# SCH_DISPLAY_T12.net
KiCad netlist of a schematic drawn in Altium Designer
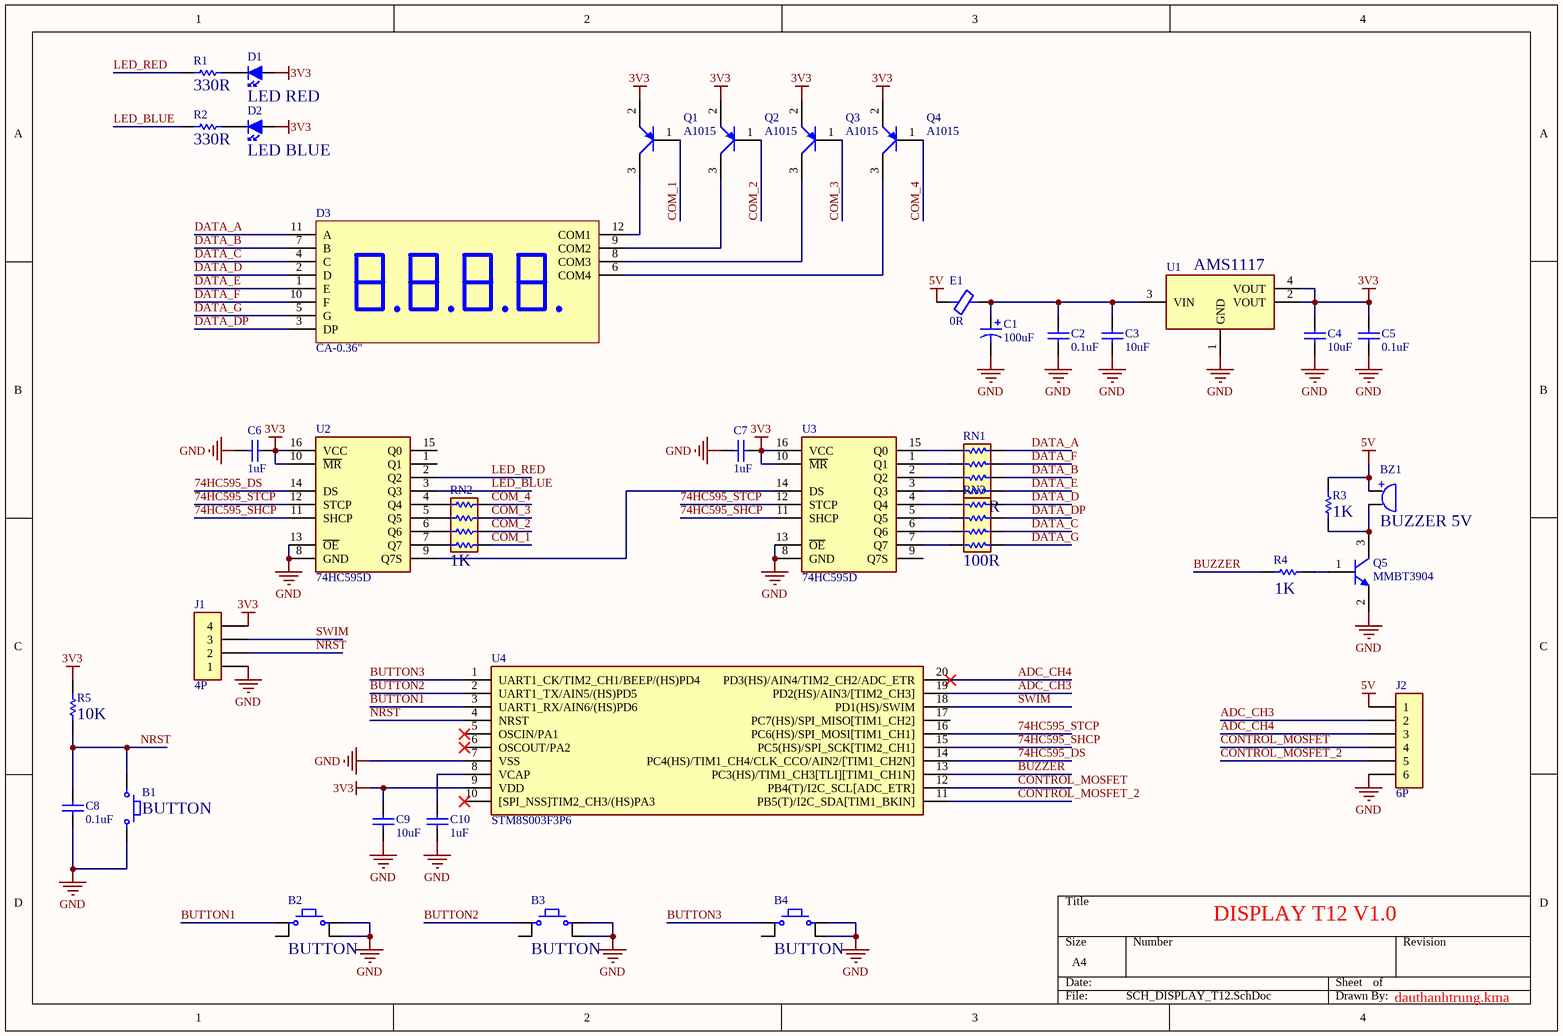
[diagram p0: SCH_DISPLAY_T12.SchDoc]

(export (version "E")
  (design (tool "Eeschema 10.0.6"))
  (components
    (comp (ref "B1")
      (value "BUTTON")
      (footprint "BUTTON-SMD-2P-3x6x2.5MM")
      (description "Nút nhấn 2 chân dán 3x6x2.5mm")
      (fields (field (name "PARTNUMBER") "CLA1750") (field (name "CREATOR") "dauthanhtrung.kma"))
      (libsource (lib "KMA-lib") (part "BUTTON-2PIN"))
    )
    (comp (ref "B2")
      (value "BUTTON")
      (footprint "BUTTON-SMD-4P-6X6X5MM")
      (description "Nút nhấn 4 chân 6x6x5mm SMD")
      (fields (field (name "PARTNUMBER") "CLA1760") (field (name "CREATOR") "dauthanhtrung.kma"))
      (libsource (lib "KMA-lib") (part "BUTTON-4PIN"))
    )
    (comp (ref "B3")
      (value "BUTTON")
      (footprint "BUTTON-SMD-4P-6X6X5MM")
      (description "Nút nhấn 4 chân 6x6x5mm SMD")
      (fields (field (name "PARTNUMBER") "CLA1760") (field (name "CREATOR") "dauthanhtrung.kma"))
      (libsource (lib "KMA-lib") (part "BUTTON-4PIN"))
    )
    (comp (ref "B4")
      (value "BUTTON")
      (footprint "BUTTON-SMD-4P-6X6X5MM")
      (description "Nút nhấn 4 chân 6x6x5mm SMD")
      (fields (field (name "PARTNUMBER") "CLA1760") (field (name "CREATOR") "dauthanhtrung.kma"))
      (libsource (lib "KMA-lib") (part "BUTTON-4PIN"))
    )
    (comp (ref "BZ1")
      (value "BUZZER 5V")
      (footprint "BUZZER_12095")
      (description "Còi chíp 5V 12095 12x9.5mm")
      (fields (field (name "PARTNUMBER") "CLA2022") (field (name "CREATOR") "dauthanhtrung.kma"))
      (libsource (lib "KMA-lib") (part "BUZZER"))
    )
    (comp (ref "C1")
      (value "100uF")
      (footprint "CAPP-ALU-SMD-6MM")
      (description "Tụ nhôm 16V 100uF 6.3x5.4mm")
      (fields (field (name "PARTNUMBER") "CLA1046") (field (name "CREATOR") "dauthanhtrung.kma"))
      (libsource (lib "KMA-lib") (part "CAPP"))
    )
    (comp (ref "C2")
      (value "0.1uF")
      (footprint "CAP_0603")
      (description "Tụ dán 0603 104-100nF 0.1uF 50V 10%")
      (fields (field (name "PARTNUMBER") "CLA4098") (field (name "CREATOR") "dauthanhtrung.kma"))
      (libsource (lib "KMA-lib") (part "CAP"))
    )
    (comp (ref "C3")
      (value "10uF")
      (footprint "CAP_0805")
      (description "Tụ dán 0805 106-10uF 16V 10%")
      (fields (field (name "PARTNUMBER") "CLA4020") (field (name "CREATOR") "dauthanhtrung.kma"))
      (libsource (lib "KMA-lib") (part "CAP"))
    )
    (comp (ref "C4")
      (value "10uF")
      (footprint "CAP_0805")
      (description "Tụ dán 0805 106-10uF 16V 10%")
      (fields (field (name "PARTNUMBER") "CLA4020") (field (name "CREATOR") "dauthanhtrung.kma"))
      (libsource (lib "KMA-lib") (part "CAP"))
    )
    (comp (ref "C5")
      (value "0.1uF")
      (footprint "CAP_0603")
      (description "Tụ dán 0603 104-100nF 0.1uF 50V 10%")
      (fields (field (name "PARTNUMBER") "CLA4098") (field (name "CREATOR") "dauthanhtrung.kma"))
      (libsource (lib "KMA-lib") (part "CAP"))
    )
    (comp (ref "C6")
      (value "1uF")
      (footprint "CAP_0603")
      (description "Tụ dán 0603 105-1uF 25V 10%")
      (fields (field (name "PARTNUMBER") "CLA4103") (field (name "CREATOR") "dauthanhtrung.kma"))
      (libsource (lib "KMA-lib") (part "CAP"))
    )
    (comp (ref "C7")
      (value "1uF")
      (footprint "CAP_0603")
      (description "Tụ dán 0603 105-1uF 25V 10%")
      (fields (field (name "PARTNUMBER") "CLA4103") (field (name "CREATOR") "dauthanhtrung.kma"))
      (libsource (lib "KMA-lib") (part "CAP"))
    )
    (comp (ref "C8")
      (value "0.1uF")
      (footprint "CAP_0603")
      (description "Tụ dán 0603 104-100nF 0.1uF 50V 10%")
      (fields (field (name "PARTNUMBER") "CLA4098") (field (name "CREATOR") "dauthanhtrung.kma"))
      (libsource (lib "KMA-lib") (part "CAP"))
    )
    (comp (ref "C9")
      (value "10uF")
      (footprint "CAP_0805")
      (description "Tụ dán 0805 106-10uF 16V 10%")
      (fields (field (name "PARTNUMBER") "CLA4020") (field (name "CREATOR") "dauthanhtrung.kma"))
      (libsource (lib "KMA-lib") (part "CAP"))
    )
    (comp (ref "C10")
      (value "1uF")
      (footprint "CAP_0603")
      (description "Tụ dán 0603 105-1uF 25V 10%")
      (fields (field (name "PARTNUMBER") "CLA4103") (field (name "CREATOR") "dauthanhtrung.kma"))
      (libsource (lib "KMA-lib") (part "CAP"))
    )
    (comp (ref "D1")
      (value "LED RED")
      (footprint "LED-0603-RED")
      (description "LED dán 0603 màu đỏ")
      (fields (field (name "PARTNUMBER") "CLA3853") (field (name "CREATOR") "dauthanhtrung.kma"))
      (libsource (lib "KMA-lib") (part "LED"))
    )
    (comp (ref "D2")
      (value "LED BLUE")
      (footprint "LED-0603-BLUE")
      (description "LED dán 0603 màu xanh dương")
      (fields (field (name "PARTNUMBER") "CLA3855") (field (name "CREATOR") "dauthanhtrung.kma"))
      (libsource (lib "KMA-lib") (part "LED"))
    )
    (comp (ref "D3")
      (value "CA-0.36\"")
      (footprint "LED7SEG-0.36-4")
      (description "LED 7 thanh 0.36 inch 4 số màu đỏ A chung 3642BS")
      (fields (field (name "PARTNUMBER") "CLA2087") (field (name "CREATOR") "dauthanhtrung.kma"))
      (libsource (lib "KMA-lib") (part "LED7SEG-0.36-4"))
    )
    (comp (ref "E1")
      (value "0R")
      (footprint "FB_0805")
      (description "Ferrite Beads 0805 0R")
      (fields (field (name "PARTNUMBER") "CL07788") (field (name "CREATOR") "dauthanhtrung.kma"))
      (libsource (lib "KMA-lib") (part "FB"))
    )
    (comp (ref "J1")
      (value "4P")
      (footprint "JUMP-2.54-MALE-4P")
      (description "Jump đực đơn 2.54mm 4P chân thẳng")
      (fields (field (name "PARTNUMBER") "JUMP-2.54-MALE-4P") (field (name "CREATOR") "dauthanhtrung.kma"))
      (libsource (lib "KMA-lib") (part "CON-4PIN"))
    )
    (comp (ref "J2")
      (value "6P")
      (footprint "XH2.54-6P")
      (description "Header đực 6P XH2.54-6P chân thẳng")
      (fields (field (name "PARTNUMBER") "CLA1882") (field (name "CREATOR") "dauthanhtrung.kma"))
      (libsource (lib "KMA-lib") (part "CON-6PIN"))
    )
    (comp (ref "Q1")
      (value "A1015")
      (footprint "SOT-23-132")
      (description "A1015 PNP Transistor 0.15A 60V SOT-23")
      (fields (field (name "PARTNUMBER") "CL08753") (field (name "CREATOR") "dauthanhtrung.kma"))
      (libsource (lib "KMA-lib") (part "PNP"))
    )
    (comp (ref "Q2")
      (value "A1015")
      (footprint "SOT-23-132")
      (description "A1015 PNP Transistor 0.15A 60V SOT-23")
      (fields (field (name "PARTNUMBER") "CL08753") (field (name "CREATOR") "dauthanhtrung.kma"))
      (libsource (lib "KMA-lib") (part "PNP"))
    )
    (comp (ref "Q3")
      (value "A1015")
      (footprint "SOT-23-132")
      (description "A1015 PNP Transistor 0.15A 60V SOT-23")
      (fields (field (name "PARTNUMBER") "CL08753") (field (name "CREATOR") "dauthanhtrung.kma"))
      (libsource (lib "KMA-lib") (part "PNP"))
    )
    (comp (ref "Q4")
      (value "A1015")
      (footprint "SOT-23-132")
      (description "A1015 PNP Transistor 0.15A 60V SOT-23")
      (fields (field (name "PARTNUMBER") "CL08753") (field (name "CREATOR") "dauthanhtrung.kma"))
      (libsource (lib "KMA-lib") (part "PNP"))
    )
    (comp (ref "Q5")
      (value "MMBT3904")
      (footprint "SOT-23-132")
      (description "2N3904 MMBT3904 1AM NPN Transistor 0.2A 40V SOT-23")
      (fields (field (name "PARTNUMBER") "CL00042") (field (name "CREATOR") "dauthanhtrung.kma"))
      (libsource (lib "KMA-lib") (part "NPN"))
    )
    (comp (ref "R1")
      (value "330R")
      (footprint "RES_0603")
      (description "Điện trở dán 0603 330R 1%")
      (fields (field (name "PARTNUMBER") "CL06621") (field (name "CREATOR") "dauthanhtrung.kma"))
      (libsource (lib "KMA-lib") (part "RES"))
    )
    (comp (ref "R2")
      (value "330R")
      (footprint "RES_0603")
      (description "Điện trở dán 0603 330R 1%")
      (fields (field (name "PARTNUMBER") "CL06621") (field (name "CREATOR") "dauthanhtrung.kma"))
      (libsource (lib "KMA-lib") (part "RES"))
    )
    (comp (ref "R3")
      (value "1K")
      (footprint "RES_0603")
      (description "Điện trở dán 0603 1K 1%")
      (fields (field (name "PARTNUMBER") "CLA0742") (field (name "CREATOR") "dauthanhtrung.kma"))
      (libsource (lib "KMA-lib") (part "RES"))
    )
    (comp (ref "R4")
      (value "1K")
      (footprint "RES_0603")
      (description "Điện trở dán 0603 1K 1%")
      (fields (field (name "PARTNUMBER") "CLA0742") (field (name "CREATOR") "dauthanhtrung.kma"))
      (libsource (lib "KMA-lib") (part "RES"))
    )
    (comp (ref "R5")
      (value "10K")
      (footprint "RES_0603")
      (description "Điện trở dán 0603 10K 1%")
      (fields (field (name "PARTNUMBER") "CLA0759") (field (name "CREATOR") "dauthanhtrung.kma"))
      (libsource (lib "KMA-lib") (part "RES"))
    )
    (comp (ref "RN1")
      (value "100R")
      (footprint "RES_ARRAY_0603X4")
      (description "Điện trở băng 0603x4 100R 8P4R")
      (fields (field (name "PARTNUMBER") "CLA0906") (field (name "CREATOR") "dauthanhtrung.kma"))
      (libsource (lib "") (part "RES-ARRAY_1"))
    )
    (comp (ref "RN2")
      (value "1K")
      (footprint "RES_ARRAY_0603X4")
      (description "Điện trở băng 0603x4 1K 8P4R")
      (fields (field (name "PARTNUMBER") "CLA0909") (field (name "CREATOR") "dauthanhtrung.kma"))
      (libsource (lib "KMA-lib") (part "RES-ARRAY"))
    )
    (comp (ref "RN3")
      (value "100R")
      (footprint "RES_ARRAY_0603X4")
      (description "Điện trở băng 0603x4 100R 8P4R")
      (fields (field (name "PARTNUMBER") "CLA0906") (field (name "CREATOR") "dauthanhtrung.kma"))
      (libsource (lib "") (part "RES-ARRAY_1"))
    )
    (comp (ref "U1")
      (value "AMS1117")
      (footprint "SOT-223")
      (description "AMS1117-3.3V IC ổn áp 3.3V 1A SOT-223")
      (fields (field (name "PARTNUMBER") "CL00249") (field (name "CREATOR") "dauthanhtrung.kma"))
      (libsource (lib "KMA-lib") (part "AMS1117"))
    )
    (comp (ref "U2")
      (value "74HC595D")
      (footprint "SOIC-16")
      (description "74HC595D SOP-16 3.9mm chính hãng NXP")
      (fields
        (field (name "MP") "STM8S003F3P6")
        (field (name "MF") "STMicroelectronics")
        (field (name "CREATOR") "dauthanhtrung.kma")
      )
      (libsource (lib "KMA-lib") (part "74HC595"))
    )
    (comp (ref "U3")
      (value "74HC595D")
      (footprint "SOIC-16")
      (description "74HC595D SOP-16 3.9mm chính hãng NXP")
      (fields
        (field (name "MP") "STM8S003F3P6")
        (field (name "MF") "STMicroelectronics")
        (field (name "CREATOR") "dauthanhtrung.kma")
      )
      (libsource (lib "KMA-lib") (part "74HC595"))
    )
    (comp (ref "U4")
      (value "STM8S003F3P6")
      (footprint "TSSOP-20")
      (description "STM8S003F3P6 TSSOP-20")
      (fields
        (field (name "MF") "STMicroelectronics")
        (field (name "PARTNUMBER") "CL00897")
        (field (name "CREATOR") "dauthanhtrung.kma")
      )
      (libsource (lib "KMA-lib") (part "STM8S003F3P6"))
    )
  )
  (nets
    (net (code "1") (name "/74HC595_DS") (class "Default")
      (node (ref "U2") (pin "14") (pinfunction "DS_14") (pintype "passive"))
      (node (ref "U4") (pin "14") (pinfunction "PC4(HS)/TIM1_CH4/CLK_CCO/AIN2/[TIM1_CH2N]_14") (pintype "passive"))
    )
    (net (code "2") (name "/74HC595_SHCP") (class "Default")
      (node (ref "U2") (pin "11") (pinfunction "SHCP_11") (pintype "passive"))
      (node (ref "U3") (pin "11") (pinfunction "SHCP_11") (pintype "passive"))
      (node (ref "U4") (pin "15") (pinfunction "PC5(HS)/SPI_SCK[TIM2_CH1]_15") (pintype "passive"))
    )
    (net (code "3") (name "/74HC595_STCP") (class "Default")
      (node (ref "U2") (pin "12") (pinfunction "STCP_12") (pintype "passive"))
      (node (ref "U3") (pin "12") (pinfunction "STCP_12") (pintype "passive"))
      (node (ref "U4") (pin "16") (pinfunction "PC6(HS)/SPI_MOSI[TIM1_CH1]_16") (pintype "passive"))
    )
    (net (code "4") (name "/ADC_CH3") (class "Default")
      (node (ref "J2") (pin "2") (pinfunction "2_2") (pintype "passive"))
      (node (ref "U4") (pin "19") (pinfunction "PD2(HS)/AIN3/[TIM2_CH3]_19") (pintype "passive"))
    )
    (net (code "5") (name "/ADC_CH4") (class "Default")
      (node (ref "J2") (pin "3") (pinfunction "3_3") (pintype "passive"))
      (node (ref "U4") (pin "20") (pinfunction "PD3(HS)/AIN4/TIM2_CH2/ADC_ETR_20") (pintype "passive"))
    )
    (net (code "6") (name "/BUTTON1") (class "Default")
      (node (ref "B2") (pin "1") (pinfunction "1_1") (pintype "passive"))
      (node (ref "U4") (pin "3") (pinfunction "UART1_RX/AIN6/(HS)PD6_3") (pintype "passive"))
    )
    (net (code "7") (name "/BUTTON2") (class "Default")
      (node (ref "B3") (pin "1") (pinfunction "1_1") (pintype "passive"))
      (node (ref "U4") (pin "2") (pinfunction "UART1_TX/AIN5/(HS)PD5_2") (pintype "passive"))
    )
    (net (code "8") (name "/BUTTON3") (class "Default")
      (node (ref "B4") (pin "1") (pinfunction "1_1") (pintype "passive"))
      (node (ref "U4") (pin "1") (pinfunction "UART1_CK/TIM2_CH1/BEEP/(HS)PD4_1") (pintype "passive"))
    )
    (net (code "9") (name "/BUZZER") (class "Default")
      (node (ref "R4") (pin "1") (pinfunction "1_1") (pintype "passive"))
      (node (ref "U4") (pin "13") (pinfunction "PC3(HS)/TIM1_CH3[TLI][TIM1_CH1N]_13") (pintype "passive"))
    )
    (net (code "10") (name "/COM_1") (class "Default")
      (node (ref "Q1") (pin "1") (pinfunction "B_1") (pintype "passive"))
      (node (ref "RN2") (pin "1") (pinfunction "1_1") (pintype "passive"))
    )
    (net (code "11") (name "/COM_2") (class "Default")
      (node (ref "Q2") (pin "1") (pinfunction "B_1") (pintype "passive"))
      (node (ref "RN2") (pin "2") (pinfunction "2_2") (pintype "passive"))
    )
    (net (code "12") (name "/COM_3") (class "Default")
      (node (ref "Q3") (pin "1") (pinfunction "B_1") (pintype "passive"))
      (node (ref "RN2") (pin "3") (pinfunction "3_3") (pintype "passive"))
    )
    (net (code "13") (name "/COM_4") (class "Default")
      (node (ref "Q4") (pin "1") (pinfunction "B_1") (pintype "passive"))
      (node (ref "RN2") (pin "4") (pinfunction "4_4") (pintype "passive"))
    )
    (net (code "14") (name "/CONTROL_MOSFET") (class "Default")
      (node (ref "J2") (pin "4") (pinfunction "4_4") (pintype "passive"))
      (node (ref "U4") (pin "12") (pinfunction "PB4(T)/I2C_SCL[ADC_ETR]_12") (pintype "passive"))
    )
    (net (code "15") (name "/CONTROL_MOSFET_2") (class "Default")
      (node (ref "J2") (pin "5") (pinfunction "5_5") (pintype "passive"))
      (node (ref "U4") (pin "11") (pinfunction "PB5(T)/I2C_SDA[TIM1_BKIN]_11") (pintype "passive"))
    )
    (net (code "16") (name "/DATA_A") (class "Default")
      (node (ref "D3") (pin "11") (pinfunction "A_11") (pintype "passive"))
      (node (ref "RN1") (pin "1") (pinfunction "1_1") (pintype "passive"))
    )
    (net (code "17") (name "/DATA_B") (class "Default")
      (node (ref "D3") (pin "7") (pinfunction "B_7") (pintype "passive"))
      (node (ref "RN1") (pin "3") (pinfunction "3_3") (pintype "passive"))
    )
    (net (code "18") (name "/DATA_C") (class "Default")
      (node (ref "D3") (pin "4") (pinfunction "C_4") (pintype "passive"))
      (node (ref "RN3") (pin "3") (pinfunction "3_3") (pintype "passive"))
    )
    (net (code "19") (name "/DATA_D") (class "Default")
      (node (ref "D3") (pin "2") (pinfunction "D_2") (pintype "passive"))
      (node (ref "RN3") (pin "1") (pinfunction "1_1") (pintype "passive"))
    )
    (net (code "20") (name "/DATA_DP") (class "Default")
      (node (ref "D3") (pin "3") (pinfunction "DP_3") (pintype "passive"))
      (node (ref "RN3") (pin "2") (pinfunction "2_2") (pintype "passive"))
    )
    (net (code "21") (name "/DATA_E") (class "Default")
      (node (ref "D3") (pin "1") (pinfunction "E_1") (pintype "passive"))
      (node (ref "RN1") (pin "4") (pinfunction "4_4") (pintype "passive"))
    )
    (net (code "22") (name "/DATA_F") (class "Default")
      (node (ref "D3") (pin "10") (pinfunction "F_10") (pintype "passive"))
      (node (ref "RN1") (pin "2") (pinfunction "2_2") (pintype "passive"))
    )
    (net (code "23") (name "/DATA_G") (class "Default")
      (node (ref "D3") (pin "5") (pinfunction "G_5") (pintype "passive"))
      (node (ref "RN3") (pin "4") (pinfunction "4_4") (pintype "passive"))
    )
    (net (code "24") (name "/LED_BLUE") (class "Default")
      (node (ref "R2") (pin "1") (pinfunction "1_1") (pintype "passive"))
      (node (ref "U2") (pin "3") (pinfunction "Q3_3") (pintype "passive"))
    )
    (net (code "25") (name "/LED_RED") (class "Default")
      (node (ref "R1") (pin "1") (pinfunction "1_1") (pintype "passive"))
      (node (ref "U2") (pin "2") (pinfunction "Q2_2") (pintype "passive"))
    )
    (net (code "26") (name "/NRST") (class "Default")
      (node (ref "B1") (pin "1") (pinfunction "1_1") (pintype "passive"))
      (node (ref "C8") (pin "1") (pinfunction "1_1") (pintype "passive"))
      (node (ref "J1") (pin "2") (pinfunction "2_2") (pintype "passive"))
      (node (ref "R5") (pin "2") (pinfunction "2_2") (pintype "passive"))
      (node (ref "U4") (pin "4") (pinfunction "NRST_4") (pintype "passive"))
    )
    (net (code "27") (name "/SWIM") (class "Default")
      (node (ref "J1") (pin "3") (pinfunction "3_3") (pintype "passive"))
      (node (ref "U4") (pin "18") (pinfunction "PD1(HS)/SWIM_18") (pintype "passive"))
    )
    (net (code "28") (name "3V3") (class "Default")
      (node (ref "C4") (pin "2") (pinfunction "2_2") (pintype "passive"))
      (node (ref "C5") (pin "2") (pinfunction "2_2") (pintype "passive"))
      (node (ref "C6") (pin "2") (pinfunction "2_2") (pintype "passive"))
      (node (ref "C7") (pin "2") (pinfunction "2_2") (pintype "passive"))
      (node (ref "C9") (pin "2") (pinfunction "2_2") (pintype "passive"))
      (node (ref "D1") (pin "1") (pinfunction "A_1") (pintype "passive"))
      (node (ref "D2") (pin "1") (pinfunction "A_1") (pintype "passive"))
      (node (ref "J1") (pin "4") (pinfunction "4_4") (pintype "passive"))
      (node (ref "Q1") (pin "2") (pinfunction "E_2") (pintype "passive"))
      (node (ref "Q2") (pin "2") (pinfunction "E_2") (pintype "passive"))
      (node (ref "Q3") (pin "2") (pinfunction "E_2") (pintype "passive"))
      (node (ref "Q4") (pin "2") (pinfunction "E_2") (pintype "passive"))
      (node (ref "R5") (pin "1") (pinfunction "1_1") (pintype "passive"))
      (node (ref "U1") (pin "2") (pinfunction "VOUT_2") (pintype "passive"))
      (node (ref "U1") (pin "4") (pinfunction "VOUT_4") (pintype "passive"))
      (node (ref "U2") (pin "10") (pinfunction "~{MR}_10") (pintype "passive"))
      (node (ref "U2") (pin "16") (pinfunction "VCC_16") (pintype "passive"))
      (node (ref "U3") (pin "10") (pinfunction "~{MR}_10") (pintype "passive"))
      (node (ref "U3") (pin "16") (pinfunction "VCC_16") (pintype "passive"))
      (node (ref "U4") (pin "9") (pinfunction "VDD_9") (pintype "passive"))
    )
    (net (code "29") (name "5V") (class "Default")
      (node (ref "BZ1") (pin "1") (pinfunction "1_1") (pintype "passive"))
      (node (ref "E1") (pin "1") (pinfunction "1_1") (pintype "passive"))
      (node (ref "J2") (pin "1") (pinfunction "1_1") (pintype "passive"))
      (node (ref "R3") (pin "2") (pinfunction "2_2") (pintype "passive"))
    )
    (net (code "30") (name "GND") (class "Default")
      (node (ref "B1") (pin "2") (pinfunction "2_2") (pintype "passive"))
      (node (ref "B2") (pin "2") (pinfunction "2_2") (pintype "passive"))
      (node (ref "B2") (pin "4") (pinfunction "4_4") (pintype "passive"))
      (node (ref "B3") (pin "2") (pinfunction "2_2") (pintype "passive"))
      (node (ref "B3") (pin "4") (pinfunction "4_4") (pintype "passive"))
      (node (ref "B4") (pin "2") (pinfunction "2_2") (pintype "passive"))
      (node (ref "B4") (pin "4") (pinfunction "4_4") (pintype "passive"))
      (node (ref "C1") (pin "2") (pinfunction "-_2") (pintype "passive"))
      (node (ref "C10") (pin "1") (pinfunction "1_1") (pintype "passive"))
      (node (ref "C2") (pin "1") (pinfunction "1_1") (pintype "passive"))
      (node (ref "C3") (pin "1") (pinfunction "1_1") (pintype "passive"))
      (node (ref "C4") (pin "1") (pinfunction "1_1") (pintype "passive"))
      (node (ref "C5") (pin "1") (pinfunction "1_1") (pintype "passive"))
      (node (ref "C6") (pin "1") (pinfunction "1_1") (pintype "passive"))
      (node (ref "C7") (pin "1") (pinfunction "1_1") (pintype "passive"))
      (node (ref "C8") (pin "2") (pinfunction "2_2") (pintype "passive"))
      (node (ref "C9") (pin "1") (pinfunction "1_1") (pintype "passive"))
      (node (ref "J1") (pin "1") (pinfunction "1_1") (pintype "passive"))
      (node (ref "J2") (pin "6") (pinfunction "6_6") (pintype "passive"))
      (node (ref "Q5") (pin "2") (pinfunction "E_2") (pintype "passive"))
      (node (ref "U1") (pin "1") (pinfunction "GND_1") (pintype "power_in"))
      (node (ref "U2") (pin "13") (pinfunction "~{OE}_13") (pintype "passive"))
      (node (ref "U2") (pin "8") (pinfunction "GND_8") (pintype "passive"))
      (node (ref "U3") (pin "13") (pinfunction "~{OE}_13") (pintype "passive"))
      (node (ref "U3") (pin "8") (pinfunction "GND_8") (pintype "passive"))
      (node (ref "U4") (pin "7") (pinfunction "VSS_7") (pintype "passive"))
    )
    (net (code "31") (name "Net-(C1-+)") (class "Default")
      (node (ref "C1") (pin "1") (pinfunction "+_1") (pintype "passive"))
      (node (ref "C2") (pin "2") (pinfunction "2_2") (pintype "passive"))
      (node (ref "C3") (pin "2") (pinfunction "2_2") (pintype "passive"))
      (node (ref "E1") (pin "2") (pinfunction "2_2") (pintype "passive"))
      (node (ref "U1") (pin "3") (pinfunction "VIN_3") (pintype "passive"))
    )
    (net (code "32") (name "Net-(D1-K)") (class "Default")
      (node (ref "D1") (pin "2") (pinfunction "K_2") (pintype "passive"))
      (node (ref "R1") (pin "2") (pinfunction "2_2") (pintype "passive"))
    )
    (net (code "33") (name "Net-(D2-K)") (class "Default")
      (node (ref "D2") (pin "2") (pinfunction "K_2") (pintype "passive"))
      (node (ref "R2") (pin "2") (pinfunction "2_2") (pintype "passive"))
    )
    (net (code "34") (name "Net-(D3-COM1)") (class "Default")
      (node (ref "D3") (pin "12") (pinfunction "COM1_12") (pintype "passive"))
      (node (ref "Q1") (pin "3") (pinfunction "C_3") (pintype "passive"))
    )
    (net (code "35") (name "Net-(D3-COM2)") (class "Default")
      (node (ref "D3") (pin "9") (pinfunction "COM2_9") (pintype "passive"))
      (node (ref "Q2") (pin "3") (pinfunction "C_3") (pintype "passive"))
    )
    (net (code "36") (name "Net-(D3-COM3)") (class "Default")
      (node (ref "D3") (pin "8") (pinfunction "COM3_8") (pintype "passive"))
      (node (ref "Q3") (pin "3") (pinfunction "C_3") (pintype "passive"))
    )
    (net (code "37") (name "Net-(D3-COM4)") (class "Default")
      (node (ref "D3") (pin "6") (pinfunction "COM4_6") (pintype "passive"))
      (node (ref "Q4") (pin "3") (pinfunction "C_3") (pintype "passive"))
    )
    (net (code "38") (name "Net-(Q5-B)") (class "Default")
      (node (ref "Q5") (pin "1") (pinfunction "B_1") (pintype "passive"))
      (node (ref "R4") (pin "2") (pinfunction "2_2") (pintype "passive"))
    )
    (net (code "39") (name "Net-(Q5-C)") (class "Default")
      (node (ref "BZ1") (pin "2") (pinfunction "2_2") (pintype "passive"))
      (node (ref "Q5") (pin "3") (pinfunction "C_3") (pintype "passive"))
      (node (ref "R3") (pin "1") (pinfunction "1_1") (pintype "passive"))
    )
    (net (code "40") (name "Net-(U2-Q4)") (class "Default")
      (node (ref "RN2") (pin "5") (pinfunction "5_5") (pintype "passive"))
      (node (ref "U2") (pin "4") (pinfunction "Q4_4") (pintype "passive"))
    )
    (net (code "41") (name "Net-(U2-Q5)") (class "Default")
      (node (ref "RN2") (pin "6") (pinfunction "6_6") (pintype "passive"))
      (node (ref "U2") (pin "5") (pinfunction "Q5_5") (pintype "passive"))
    )
    (net (code "42") (name "Net-(U2-Q6)") (class "Default")
      (node (ref "RN2") (pin "7") (pinfunction "7_7") (pintype "passive"))
      (node (ref "U2") (pin "6") (pinfunction "Q6_6") (pintype "passive"))
    )
    (net (code "43") (name "Net-(U2-Q7)") (class "Default")
      (node (ref "RN2") (pin "8") (pinfunction "8_8") (pintype "passive"))
      (node (ref "U2") (pin "7") (pinfunction "Q7_7") (pintype "passive"))
    )
    (net (code "44") (name "Net-(U2-Q7S)") (class "Default")
      (node (ref "U2") (pin "9") (pinfunction "Q7S_9") (pintype "passive"))
      (node (ref "U3") (pin "14") (pinfunction "DS_14") (pintype "passive"))
    )
    (net (code "45") (name "Net-(U3-Q0)") (class "Default")
      (node (ref "RN1") (pin "8") (pinfunction "8_8") (pintype "passive"))
      (node (ref "U3") (pin "15") (pinfunction "Q0_15") (pintype "passive"))
    )
    (net (code "46") (name "Net-(U3-Q1)") (class "Default")
      (node (ref "RN1") (pin "7") (pinfunction "7_7") (pintype "passive"))
      (node (ref "U3") (pin "1") (pinfunction "Q1_1") (pintype "passive"))
    )
    (net (code "47") (name "Net-(U3-Q2)") (class "Default")
      (node (ref "RN1") (pin "6") (pinfunction "6_6") (pintype "passive"))
      (node (ref "U3") (pin "2") (pinfunction "Q2_2") (pintype "passive"))
    )
    (net (code "48") (name "Net-(U3-Q3)") (class "Default")
      (node (ref "RN1") (pin "5") (pinfunction "5_5") (pintype "passive"))
      (node (ref "U3") (pin "3") (pinfunction "Q3_3") (pintype "passive"))
    )
    (net (code "49") (name "Net-(U3-Q4)") (class "Default")
      (node (ref "RN3") (pin "8") (pinfunction "8_8") (pintype "passive"))
      (node (ref "U3") (pin "4") (pinfunction "Q4_4") (pintype "passive"))
    )
    (net (code "50") (name "Net-(U3-Q5)") (class "Default")
      (node (ref "RN3") (pin "7") (pinfunction "7_7") (pintype "passive"))
      (node (ref "U3") (pin "5") (pinfunction "Q5_5") (pintype "passive"))
    )
    (net (code "51") (name "Net-(U3-Q6)") (class "Default")
      (node (ref "RN3") (pin "6") (pinfunction "6_6") (pintype "passive"))
      (node (ref "U3") (pin "6") (pinfunction "Q6_6") (pintype "passive"))
    )
    (net (code "52") (name "Net-(U3-Q7)") (class "Default")
      (node (ref "RN3") (pin "5") (pinfunction "5_5") (pintype "passive"))
      (node (ref "U3") (pin "7") (pinfunction "Q7_7") (pintype "passive"))
    )
    (net (code "53") (name "Net-(U4-VCAP)") (class "Default")
      (node (ref "C10") (pin "2") (pinfunction "2_2") (pintype "passive"))
      (node (ref "U4") (pin "8") (pinfunction "VCAP_8") (pintype "passive"))
    )
    (net (code "54") (name "unconnected-(B2-Pad3)") (class "Default")
      (node (ref "B2") (pin "3") (pinfunction "3_3") (pintype "passive"))
    )
    (net (code "55") (name "unconnected-(B3-Pad3)") (class "Default")
      (node (ref "B3") (pin "3") (pinfunction "3_3") (pintype "passive"))
    )
    (net (code "56") (name "unconnected-(B4-Pad3)") (class "Default")
      (node (ref "B4") (pin "3") (pinfunction "3_3") (pintype "passive"))
    )
    (net (code "57") (name "unconnected-(U2-Q0-Pad15)") (class "Default")
      (node (ref "U2") (pin "15") (pinfunction "Q0_15") (pintype "passive"))
    )
    (net (code "58") (name "unconnected-(U2-Q1-Pad1)") (class "Default")
      (node (ref "U2") (pin "1") (pinfunction "Q1_1") (pintype "passive"))
    )
    (net (code "59") (name "unconnected-(U3-Q7S-Pad9)") (class "Default")
      (node (ref "U3") (pin "9") (pinfunction "Q7S_9") (pintype "passive"))
    )
    (net (code "60") (name "unconnected-(U4-OSCIN{slash}PA1-Pad5)") (class "Default")
      (node (ref "U4") (pin "5") (pinfunction "OSCIN/PA1_5") (pintype "passive+no_connect"))
    )
    (net (code "61") (name "unconnected-(U4-OSCOUT{slash}PA2-Pad6)") (class "Default")
      (node (ref "U4") (pin "6") (pinfunction "OSCOUT/PA2_6") (pintype "passive+no_connect"))
    )
    (net (code "62") (name "unconnected-(U4-PC7(HS){slash}SPI_MISO[TIM1_CH2]-Pad17)") (class "Default")
      (node (ref "U4") (pin "17") (pinfunction "PC7(HS)/SPI_MISO[TIM1_CH2]_17") (pintype "passive"))
    )
    (net (code "63") (name "unconnected-(U4-[SPI_NSS]TIM2_CH3{slash}(HS)PA3-Pad10)") (class "Default")
      (node (ref "U4") (pin "10") (pinfunction "[SPI_NSS]TIM2_CH3/(HS)PA3_10") (pintype "passive+no_connect"))
    )
  )
)
